# espBoardScheme.net
KiCad netlist of a schematic drawn in EAGLE
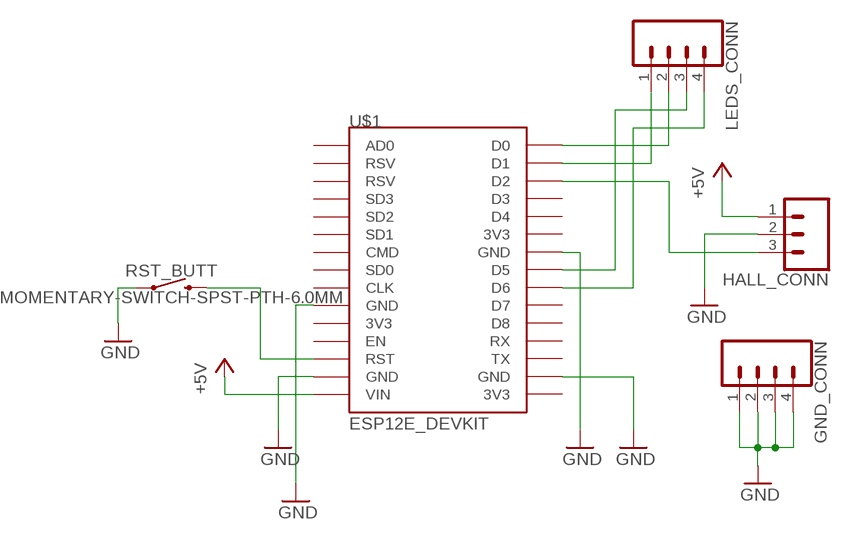
[diagram p0: schematic, sheet 1]

(export (version "E")
  (design (tool "Eeschema 10.0.6"))
  (components
    (comp (ref "GND_CONN")
      (value "CONN_04")
      (footprint "eagle-import:1X04")
      (libsource (lib "eagle-import") (part "CONN_04"))
    )
    (comp (ref "HALL_CONN")
      (value "CONN_03")
      (footprint "eagle-import:1X03")
      (libsource (lib "eagle-import") (part "CONN_03"))
    )
    (comp (ref "LEDS_CONN")
      (value "CONN_04")
      (footprint "eagle-import:1X04")
      (libsource (lib "eagle-import") (part "CONN_04"))
    )
    (comp (ref "RST_BUTT")
      (value "MOMENTARY-SWITCH-SPST-PTH-6.0MM")
      (footprint "eagle-import:TACTILE_SWITCH_PTH_6.0MM")
      (libsource (lib "eagle-import") (part "MOMENTARY-SWITCH-SPST-PTH-6.0MM"))
    )
    (comp (ref "U$1")
      (value "ESP12E_DEVKIT")
      (footprint "eagle-import:ESP12E_DEVKIT")
      (libsource (lib "eagle-import") (part "ESP12E_DEVKIT"))
    )
  )
  (nets
    (net (code "1") (name "+5V") (class "Default")
      (node (ref "HALL_CONN") (pin "1") (pinfunction "1_1") (pintype "passive"))
      (node (ref "U$1") (pin "VIN") (pinfunction "VIN_VIN") (pintype "bidirectional"))
    )
    (net (code "2") (name "GND") (class "Default")
      (node (ref "GND_CONN") (pin "1") (pinfunction "1_1") (pintype "passive"))
      (node (ref "GND_CONN") (pin "2") (pinfunction "2_2") (pintype "passive"))
      (node (ref "GND_CONN") (pin "3") (pinfunction "3_3") (pintype "passive"))
      (node (ref "GND_CONN") (pin "4") (pinfunction "4_4") (pintype "passive"))
      (node (ref "HALL_CONN") (pin "2") (pinfunction "2_2") (pintype "passive"))
      (node (ref "RST_BUTT") (pin "1") (pinfunction "1_1") (pintype "passive"))
      (node (ref "U$1") (pin "GND@0") (pinfunction "GND_GND@0") (pintype "bidirectional"))
      (node (ref "U$1") (pin "GND@1") (pinfunction "GND_GND@1") (pintype "bidirectional"))
      (node (ref "U$1") (pin "GND@2") (pinfunction "GND_GND@2") (pintype "bidirectional"))
      (node (ref "U$1") (pin "GND@3") (pinfunction "GND_GND@3") (pintype "bidirectional"))
    )
    (net (code "3") (name "Net-(HALL_CONN-Pad3)") (class "Default")
      (node (ref "HALL_CONN") (pin "3") (pinfunction "3_3") (pintype "passive"))
      (node (ref "U$1") (pin "D2") (pinfunction "D2_D2") (pintype "bidirectional"))
    )
    (net (code "4") (name "Net-(LEDS_CONN-Pad1)") (class "Default")
      (node (ref "LEDS_CONN") (pin "1") (pinfunction "1_1") (pintype "passive"))
      (node (ref "U$1") (pin "D1") (pinfunction "D1_D1") (pintype "bidirectional"))
    )
    (net (code "5") (name "Net-(LEDS_CONN-Pad2)") (class "Default")
      (node (ref "LEDS_CONN") (pin "2") (pinfunction "2_2") (pintype "passive"))
      (node (ref "U$1") (pin "D0") (pinfunction "D0_D0") (pintype "bidirectional"))
    )
    (net (code "6") (name "Net-(LEDS_CONN-Pad3)") (class "Default")
      (node (ref "LEDS_CONN") (pin "3") (pinfunction "3_3") (pintype "passive"))
      (node (ref "U$1") (pin "D5") (pinfunction "D5_D5") (pintype "bidirectional"))
    )
    (net (code "7") (name "Net-(LEDS_CONN-Pad4)") (class "Default")
      (node (ref "LEDS_CONN") (pin "4") (pinfunction "4_4") (pintype "passive"))
      (node (ref "U$1") (pin "D6") (pinfunction "D6_D6") (pintype "bidirectional"))
    )
    (net (code "8") (name "Net-(RST_BUTT-2)") (class "Default")
      (node (ref "RST_BUTT") (pin "3") (pinfunction "2_3") (pintype "passive"))
      (node (ref "U$1") (pin "RST") (pinfunction "RST_RST") (pintype "bidirectional"))
    )
    (net (code "9") (name "unconnected-(U$1-3V3-Pad3V3@0)") (class "Default")
      (node (ref "U$1") (pin "3V3@0") (pinfunction "3V3_3V3@0") (pintype "bidirectional"))
    )
    (net (code "10") (name "unconnected-(U$1-3V3-Pad3V3@1)") (class "Default")
      (node (ref "U$1") (pin "3V3@1") (pinfunction "3V3_3V3@1") (pintype "bidirectional"))
    )
    (net (code "11") (name "unconnected-(U$1-3V3-Pad3V3@2)") (class "Default")
      (node (ref "U$1") (pin "3V3@2") (pinfunction "3V3_3V3@2") (pintype "bidirectional"))
    )
    (net (code "12") (name "unconnected-(U$1-PadAD0)") (class "Default")
      (node (ref "U$1") (pin "AD0") (pinfunction "AD0_AD0") (pintype "bidirectional"))
    )
    (net (code "13") (name "unconnected-(U$1-PadCLK)") (class "Default")
      (node (ref "U$1") (pin "CLK") (pinfunction "CLK_CLK") (pintype "bidirectional"))
    )
    (net (code "14") (name "unconnected-(U$1-PadCMD)") (class "Default")
      (node (ref "U$1") (pin "CMD") (pinfunction "CMD_CMD") (pintype "bidirectional"))
    )
    (net (code "15") (name "unconnected-(U$1-PadD3)") (class "Default")
      (node (ref "U$1") (pin "D3") (pinfunction "D3_D3") (pintype "bidirectional"))
    )
    (net (code "16") (name "unconnected-(U$1-PadD4)") (class "Default")
      (node (ref "U$1") (pin "D4") (pinfunction "D4_D4") (pintype "bidirectional"))
    )
    (net (code "17") (name "unconnected-(U$1-PadD7)") (class "Default")
      (node (ref "U$1") (pin "D7") (pinfunction "D7_D7") (pintype "bidirectional"))
    )
    (net (code "18") (name "unconnected-(U$1-PadD8)") (class "Default")
      (node (ref "U$1") (pin "D8") (pinfunction "D8_D8") (pintype "bidirectional"))
    )
    (net (code "19") (name "unconnected-(U$1-PadEN)") (class "Default")
      (node (ref "U$1") (pin "EN") (pinfunction "EN_EN") (pintype "bidirectional"))
    )
    (net (code "20") (name "unconnected-(U$1-PadRX)") (class "Default")
      (node (ref "U$1") (pin "RX") (pinfunction "RX_RX") (pintype "bidirectional"))
    )
    (net (code "21") (name "unconnected-(U$1-PadSD0)") (class "Default")
      (node (ref "U$1") (pin "SD0") (pinfunction "SD0_SD0") (pintype "bidirectional"))
    )
    (net (code "22") (name "unconnected-(U$1-PadSD1)") (class "Default")
      (node (ref "U$1") (pin "SD1") (pinfunction "SD1_SD1") (pintype "bidirectional"))
    )
    (net (code "23") (name "unconnected-(U$1-PadSD2)") (class "Default")
      (node (ref "U$1") (pin "SD2") (pinfunction "SD2_SD2") (pintype "bidirectional"))
    )
    (net (code "24") (name "unconnected-(U$1-PadSD3)") (class "Default")
      (node (ref "U$1") (pin "SD3") (pinfunction "SD3_SD3") (pintype "bidirectional"))
    )
    (net (code "25") (name "unconnected-(U$1-PadTX)") (class "Default")
      (node (ref "U$1") (pin "TX") (pinfunction "TX_TX") (pintype "bidirectional"))
    )
    (net (code "26") (name "unconnected-(U$1-RSV-PadRSV@0)") (class "Default")
      (node (ref "U$1") (pin "RSV@0") (pinfunction "RSV_RSV@0") (pintype "bidirectional"))
    )
    (net (code "27") (name "unconnected-(U$1-RSV-PadRSV@1)") (class "Default")
      (node (ref "U$1") (pin "RSV@1") (pinfunction "RSV_RSV@1") (pintype "bidirectional"))
    )
  )
)
